# Project.net
KiCad netlist of a schematic drawn in EasyEDA Pro
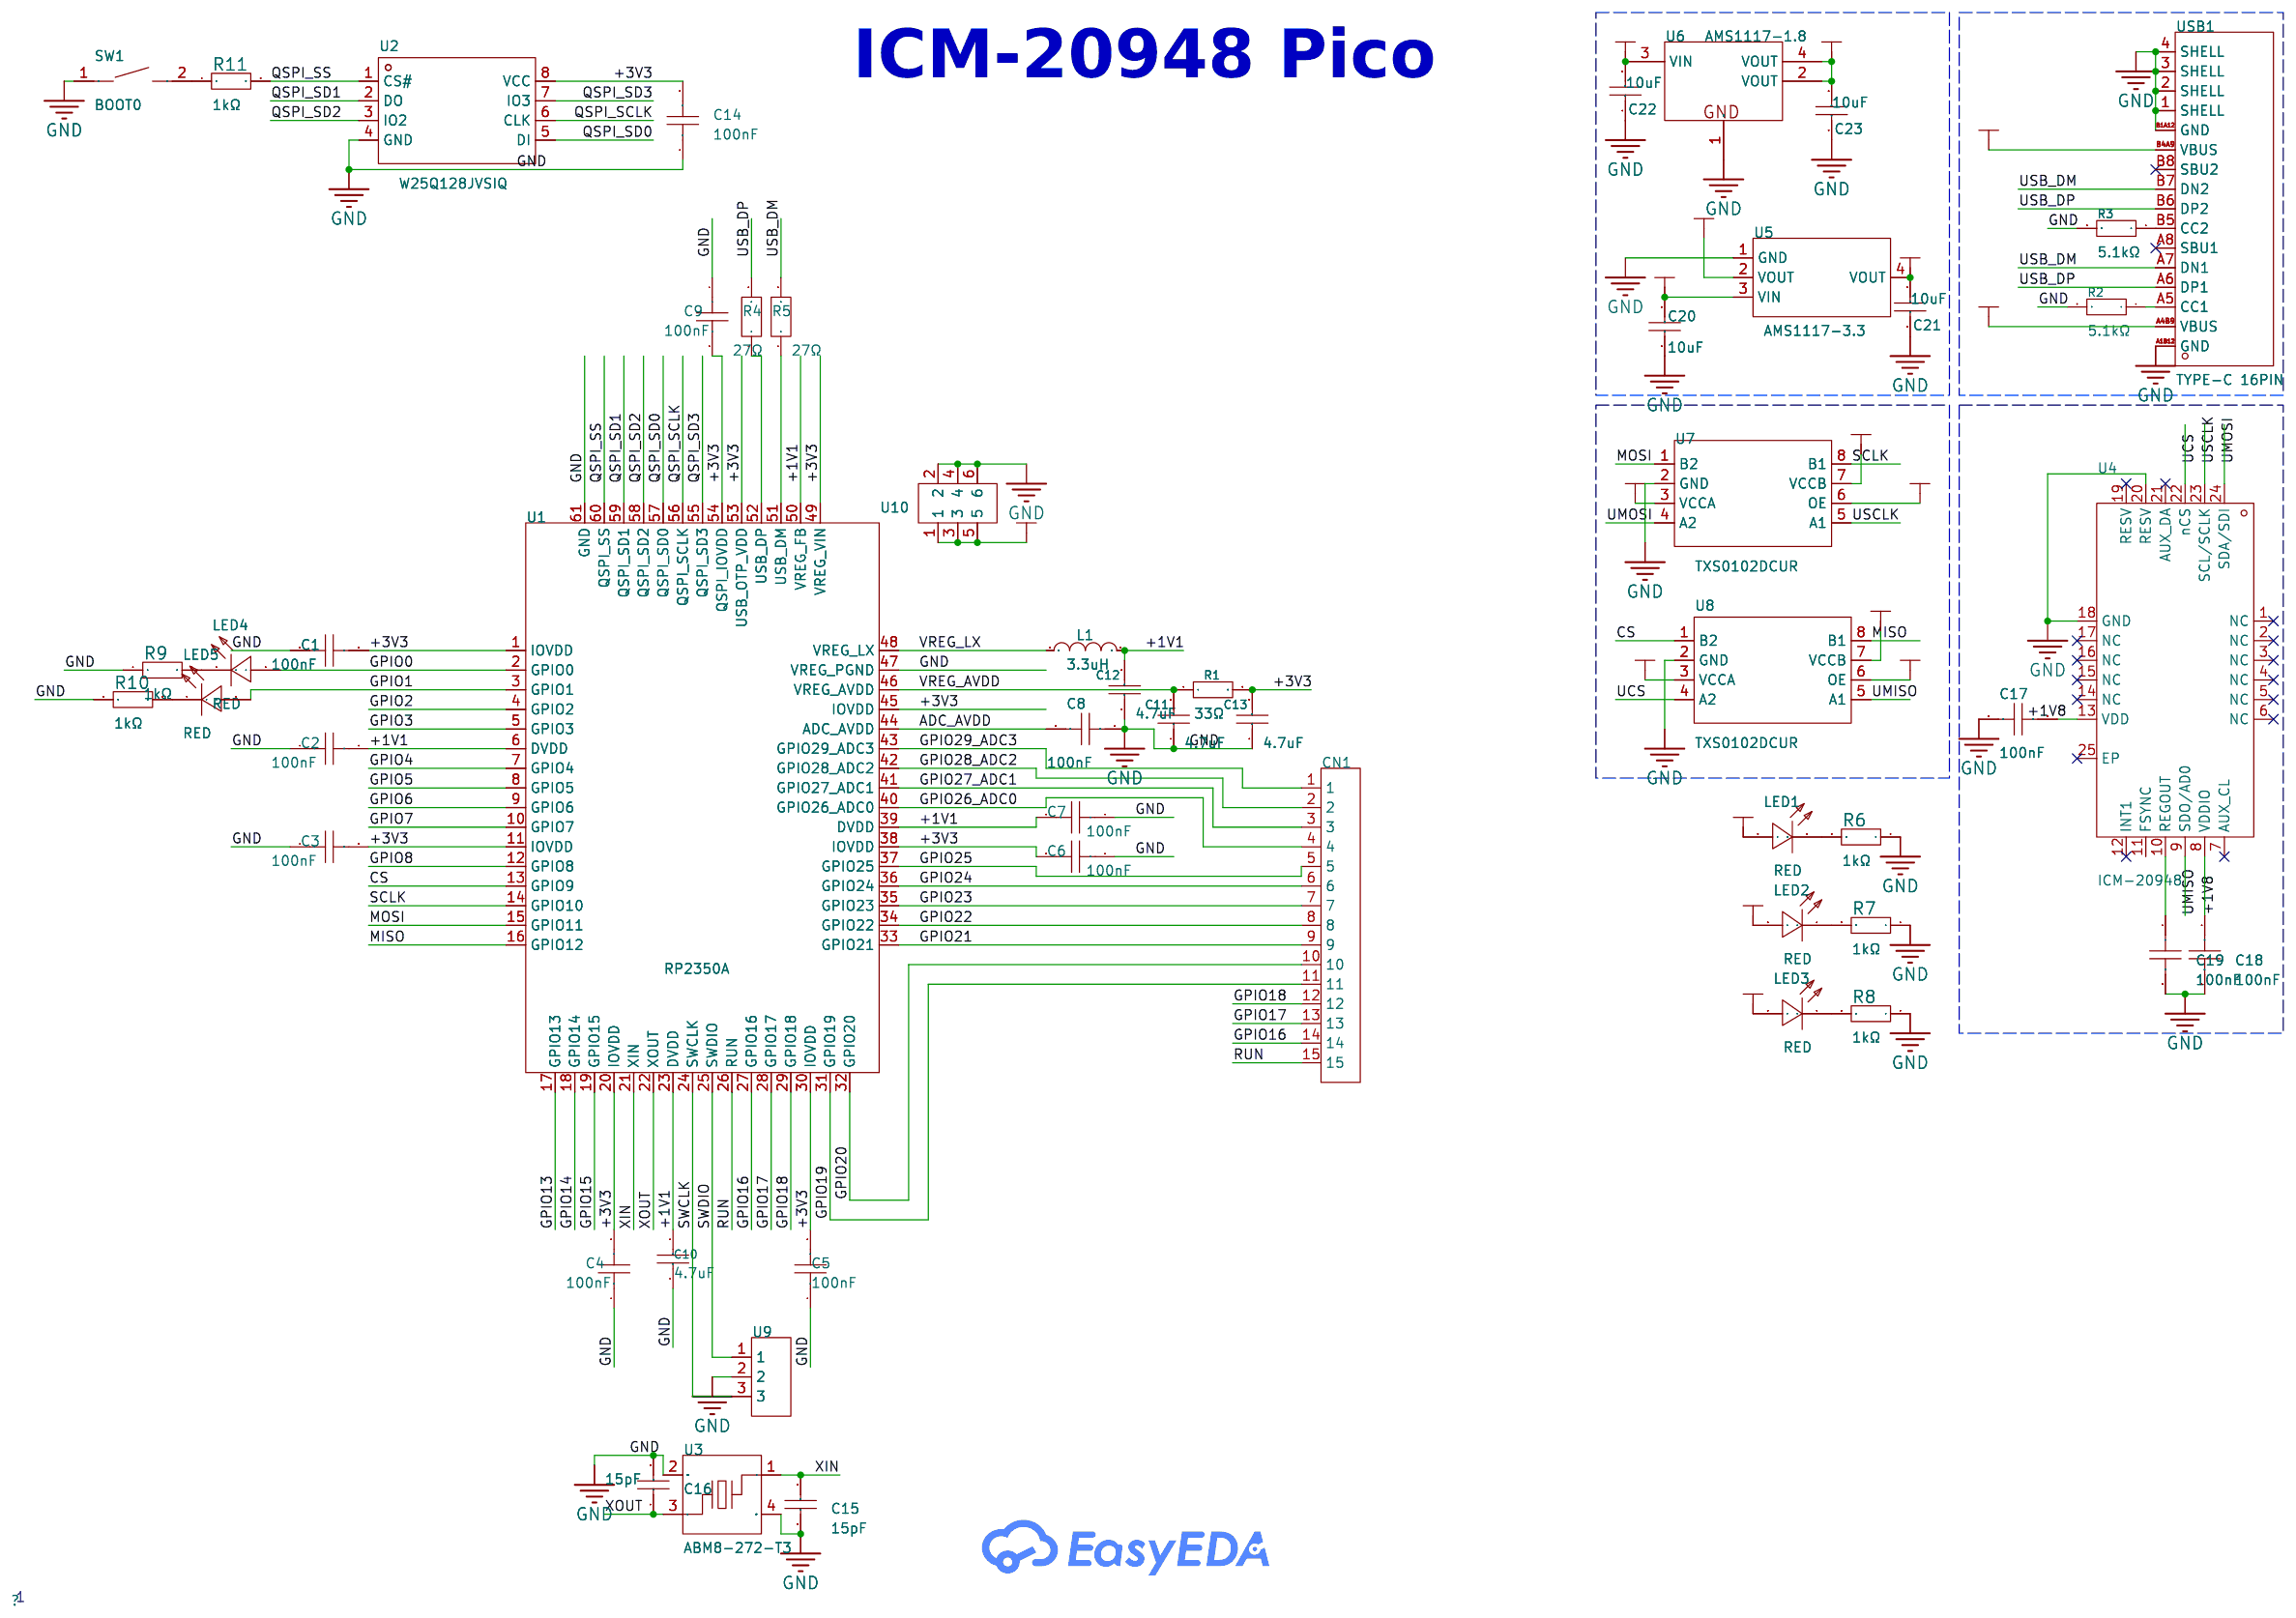
[diagram p0: schematic sheet]

(export (version "E")
  (design (tool "Eeschema 10.0.6"))
  (components
    (comp (ref "C1")
      (value "100nF")
      (footprint "easyedapro:C0402")
      (fields
        (field (name "Manufacturer Part") "CL05B104KO5NNNC")
        (field (name "Manufacturer") "SAMSUNG(三星)")
      )
      (libsource (lib "easyedapro") (part "CL05B104KO5NNNC"))
    )
    (comp (ref "C2")
      (value "100nF")
      (footprint "easyedapro:C0402")
      (fields
        (field (name "Manufacturer Part") "CL05B104KO5NNNC")
        (field (name "Manufacturer") "SAMSUNG(三星)")
      )
      (libsource (lib "easyedapro") (part "CL05B104KO5NNNC"))
    )
    (comp (ref "C3")
      (value "100nF")
      (footprint "easyedapro:C0402")
      (fields
        (field (name "Manufacturer Part") "CL05B104KO5NNNC")
        (field (name "Manufacturer") "SAMSUNG(三星)")
      )
      (libsource (lib "easyedapro") (part "CL05B104KO5NNNC"))
    )
    (comp (ref "C4")
      (value "100nF")
      (footprint "easyedapro:C0402")
      (fields
        (field (name "Manufacturer Part") "CL05B104KO5NNNC")
        (field (name "Manufacturer") "SAMSUNG(三星)")
      )
      (libsource (lib "easyedapro") (part "CL05B104KO5NNNC"))
    )
    (comp (ref "C5")
      (value "100nF")
      (footprint "easyedapro:C0402")
      (fields
        (field (name "Manufacturer Part") "CL05B104KO5NNNC")
        (field (name "Manufacturer") "SAMSUNG(三星)")
      )
      (libsource (lib "easyedapro") (part "CL05B104KO5NNNC"))
    )
    (comp (ref "C6")
      (value "100nF")
      (footprint "easyedapro:C0402")
      (fields
        (field (name "Manufacturer Part") "CL05B104KO5NNNC")
        (field (name "Manufacturer") "SAMSUNG(三星)")
      )
      (libsource (lib "easyedapro") (part "CL05B104KO5NNNC"))
    )
    (comp (ref "C7")
      (value "100nF")
      (footprint "easyedapro:C0402")
      (fields
        (field (name "Manufacturer Part") "CL05B104KO5NNNC")
        (field (name "Manufacturer") "SAMSUNG(三星)")
      )
      (libsource (lib "easyedapro") (part "CL05B104KO5NNNC"))
    )
    (comp (ref "C8")
      (value "100nF")
      (footprint "easyedapro:C0402")
      (fields
        (field (name "Manufacturer Part") "CL05B104KO5NNNC")
        (field (name "Manufacturer") "SAMSUNG(三星)")
      )
      (libsource (lib "easyedapro") (part "CL05B104KO5NNNC"))
    )
    (comp (ref "C9")
      (value "100nF")
      (footprint "easyedapro:C0402")
      (fields
        (field (name "Manufacturer Part") "CL05B104KO5NNNC")
        (field (name "Manufacturer") "SAMSUNG(三星)")
      )
      (libsource (lib "easyedapro") (part "CL05B104KO5NNNC"))
    )
    (comp (ref "C10")
      (value "4.7uF")
      (footprint "easyedapro:C0402")
      (fields
        (field (name "Manufacturer Part") "CL05A475MP5NRNC")
        (field (name "Manufacturer") "SAMSUNG(三星)")
      )
      (libsource (lib "easyedapro") (part "CL05A475MP5NRNC"))
    )
    (comp (ref "C11")
      (value "4.7uF")
      (footprint "easyedapro:C0402")
      (fields
        (field (name "Manufacturer Part") "CL05A475MP5NRNC")
        (field (name "Manufacturer") "SAMSUNG(三星)")
      )
      (libsource (lib "easyedapro") (part "CL05A475MP5NRNC"))
    )
    (comp (ref "C12")
      (value "4.7uF")
      (footprint "easyedapro:C0402")
      (fields
        (field (name "Manufacturer Part") "CL05A475MP5NRNC")
        (field (name "Manufacturer") "SAMSUNG(三星)")
      )
      (libsource (lib "easyedapro") (part "CL05A475MP5NRNC"))
    )
    (comp (ref "C13")
      (value "4.7uF")
      (footprint "easyedapro:C0402")
      (fields
        (field (name "Manufacturer Part") "CL05A475MP5NRNC")
        (field (name "Manufacturer") "SAMSUNG(三星)")
      )
      (libsource (lib "easyedapro") (part "CL05A475MP5NRNC"))
    )
    (comp (ref "C14")
      (value "100nF")
      (footprint "easyedapro:C0402")
      (fields
        (field (name "Manufacturer Part") "CL05B104KO5NNNC")
        (field (name "Manufacturer") "SAMSUNG(三星)")
      )
      (libsource (lib "easyedapro") (part "CL05B104KO5NNNC"))
    )
    (comp (ref "C15")
      (value "15pF")
      (footprint "easyedapro:C0402")
      (fields (field (name "Manufacturer Part") "0402CG150J500NT") (field (name "Manufacturer") "FH(风华)"))
      (libsource (lib "easyedapro") (part "0402CG150J500NT"))
    )
    (comp (ref "C16")
      (value "15pF")
      (footprint "easyedapro:C0402")
      (fields (field (name "Manufacturer Part") "0402CG150J500NT") (field (name "Manufacturer") "FH(风华)"))
      (libsource (lib "easyedapro") (part "0402CG150J500NT"))
    )
    (comp (ref "C17")
      (value "100nF")
      (footprint "easyedapro:C0402")
      (fields
        (field (name "Manufacturer Part") "CL05B104KO5NNNC")
        (field (name "Manufacturer") "SAMSUNG(三星)")
      )
      (libsource (lib "easyedapro") (part "CL05B104KO5NNNC"))
    )
    (comp (ref "C18")
      (value "100nF")
      (footprint "easyedapro:C0402")
      (fields
        (field (name "Manufacturer Part") "CL05B104KO5NNNC")
        (field (name "Manufacturer") "SAMSUNG(三星)")
      )
      (libsource (lib "easyedapro") (part "CL05B104KO5NNNC"))
    )
    (comp (ref "C19")
      (value "100nF")
      (footprint "easyedapro:C0402")
      (fields
        (field (name "Manufacturer Part") "CL05B104KO5NNNC")
        (field (name "Manufacturer") "SAMSUNG(三星)")
      )
      (libsource (lib "easyedapro") (part "CL05B104KO5NNNC"))
    )
    (comp (ref "C20")
      (value "10uF")
      (footprint "easyedapro:C0402")
      (fields
        (field (name "Manufacturer Part") "CL05A106MQ5NUNC")
        (field (name "Manufacturer") "SAMSUNG(三星)")
      )
      (libsource (lib "easyedapro") (part "CL05A106MQ5NUNC"))
    )
    (comp (ref "C21")
      (value "10uF")
      (footprint "easyedapro:C0402")
      (fields
        (field (name "Manufacturer Part") "CL05A106MQ5NUNC")
        (field (name "Manufacturer") "SAMSUNG(三星)")
      )
      (libsource (lib "easyedapro") (part "CL05A106MQ5NUNC"))
    )
    (comp (ref "C22")
      (value "10uF")
      (footprint "easyedapro:C0402")
      (fields
        (field (name "Manufacturer Part") "CL05A106MQ5NUNC")
        (field (name "Manufacturer") "SAMSUNG(三星)")
      )
      (libsource (lib "easyedapro") (part "CL05A106MQ5NUNC"))
    )
    (comp (ref "C23")
      (value "10uF")
      (footprint "easyedapro:C0402")
      (fields
        (field (name "Manufacturer Part") "CL05A106MQ5NUNC")
        (field (name "Manufacturer") "SAMSUNG(三星)")
      )
      (libsource (lib "easyedapro") (part "CL05A106MQ5NUNC"))
    )
    (comp (ref "CN1")
      (value "排母插针1X15P")
      (footprint "easyedapro:CONN-TH_15P-L38.5-W2.4-P2.54")
      (libsource (lib "easyedapro") (part "排母插针1X15P"))
    )
    (comp (ref "L1")
      (value "3.3uH")
      (footprint "easyedapro:IND-SMD_L2.0-W1.6_AOTA-B201610S3R3-101-T")
      (fields (field (name "Manufacturer") "ABRACON"))
      (libsource (lib "easyedapro") (part "AOTA-B201610S3R3-101-T"))
    )
    (comp (ref "LED1")
      (value "RED")
      (footprint "easyedapro:LED0603-RD")
      (fields (field (name "Manufacturer") "KENTO"))
      (libsource (lib "easyedapro") (part "KT-0603R"))
    )
    (comp (ref "LED2")
      (value "RED")
      (footprint "easyedapro:LED0603-RD")
      (fields (field (name "Manufacturer") "KENTO"))
      (libsource (lib "easyedapro") (part "KT-0603R"))
    )
    (comp (ref "LED3")
      (value "RED")
      (footprint "easyedapro:LED0603-RD")
      (fields (field (name "Manufacturer") "KENTO"))
      (libsource (lib "easyedapro") (part "KT-0603R"))
    )
    (comp (ref "LED4")
      (value "RED")
      (footprint "easyedapro:LED0603-RD")
      (fields (field (name "Manufacturer") "KENTO"))
      (libsource (lib "easyedapro") (part "KT-0603R"))
    )
    (comp (ref "LED5")
      (value "RED")
      (footprint "easyedapro:LED0603-RD")
      (fields (field (name "Manufacturer") "KENTO"))
      (libsource (lib "easyedapro") (part "KT-0603R"))
    )
    (comp (ref "R1")
      (value "33Ω")
      (footprint "easyedapro:R0402")
      (fields
        (field (name "Manufacturer Part") "0402WGF330JTCE")
        (field (name "Manufacturer") "UNI-ROYAL(厚声)")
      )
      (libsource (lib "easyedapro") (part "0402WGF330JTCE"))
    )
    (comp (ref "R2")
      (value "5.1kΩ")
      (footprint "easyedapro:R0402")
      (fields
        (field (name "Manufacturer Part") "0402WGF5101TCE")
        (field (name "Manufacturer") "UNI-ROYAL(厚声)")
      )
      (libsource (lib "easyedapro") (part "0402WGF5101TCE"))
    )
    (comp (ref "R3")
      (value "5.1kΩ")
      (footprint "easyedapro:R0402")
      (fields
        (field (name "Manufacturer Part") "0402WGF5101TCE")
        (field (name "Manufacturer") "UNI-ROYAL(厚声)")
      )
      (libsource (lib "easyedapro") (part "0402WGF5101TCE"))
    )
    (comp (ref "R4")
      (value "27Ω")
      (footprint "easyedapro:R0402")
      (fields (field (name "Manufacturer Part") "WR04X270JTL") (field (name "Manufacturer") "Walsin(华新科)"))
      (libsource (lib "easyedapro") (part "WR04X270 JTL"))
    )
    (comp (ref "R5")
      (value "27Ω")
      (footprint "easyedapro:R0402")
      (fields (field (name "Manufacturer Part") "WR04X270JTL") (field (name "Manufacturer") "Walsin(华新科)"))
      (libsource (lib "easyedapro") (part "WR04X270 JTL"))
    )
    (comp (ref "R6")
      (value "1kΩ")
      (footprint "easyedapro:R0402")
      (fields
        (field (name "Manufacturer Part") "0402WGF1001TCE")
        (field (name "Manufacturer") "UNI-ROYAL(厚声)")
      )
      (libsource (lib "easyedapro") (part "0402WGF1001TCE"))
    )
    (comp (ref "R7")
      (value "1kΩ")
      (footprint "easyedapro:R0402")
      (fields
        (field (name "Manufacturer Part") "0402WGF1001TCE")
        (field (name "Manufacturer") "UNI-ROYAL(厚声)")
      )
      (libsource (lib "easyedapro") (part "0402WGF1001TCE"))
    )
    (comp (ref "R8")
      (value "1kΩ")
      (footprint "easyedapro:R0402")
      (fields
        (field (name "Manufacturer Part") "0402WGF1001TCE")
        (field (name "Manufacturer") "UNI-ROYAL(厚声)")
      )
      (libsource (lib "easyedapro") (part "0402WGF1001TCE"))
    )
    (comp (ref "R9")
      (value "1kΩ")
      (footprint "easyedapro:R0402")
      (fields
        (field (name "Manufacturer Part") "0402WGF1001TCE")
        (field (name "Manufacturer") "UNI-ROYAL(厚声)")
      )
      (libsource (lib "easyedapro") (part "0402WGF1001TCE"))
    )
    (comp (ref "R10")
      (value "1kΩ")
      (footprint "easyedapro:R0402")
      (fields
        (field (name "Manufacturer Part") "0402WGF1001TCE")
        (field (name "Manufacturer") "UNI-ROYAL(厚声)")
      )
      (libsource (lib "easyedapro") (part "0402WGF1001TCE"))
    )
    (comp (ref "R11")
      (value "1kΩ")
      (footprint "easyedapro:R0402")
      (fields
        (field (name "Manufacturer Part") "0402WGF1001TCE")
        (field (name "Manufacturer") "UNI-ROYAL(厚声)")
      )
      (libsource (lib "easyedapro") (part "0402WGF1001TCE"))
    )
    (comp (ref "SW1")
      (value "BOOT0")
      (footprint "easyedapro:SW-SMD_L3.9-W3.0-P4.45")
      (fields (field (name "Manufacturer") "XUNPU(讯普)"))
      (libsource (lib "easyedapro") (part "TS-1088-AR02016"))
    )
    (comp (ref "U1")
      (value "RP2350A")
      (footprint "easyedapro:QFN-60_L7.0-W7.0-P0.40-TL-EP3.4")
      (fields (field (name "Manufacturer") "Raspberry Pi(树莓派)"))
      (libsource (lib "easyedapro") (part "RP2350A_C42411118"))
    )
    (comp (ref "U2")
      (value "W25Q128JVSIQ")
      (footprint "easyedapro:SOIC-8_L5.3-W5.3-P1.27-LS8.0-BL")
      (fields (field (name "Manufacturer") "WINBOND(华邦)"))
      (libsource (lib "easyedapro") (part "W25Q128JVSIQTR"))
    )
    (comp (ref "U3")
      (value "ABM8-272-T3")
      (footprint "easyedapro:CRYSTAL-SMD_4P-L3.2-W2.5-BL")
      (fields (field (name "Manufacturer") "ABRACON"))
      (libsource (lib "easyedapro") (part "ABM8-272-T3_C20625731"))
    )
    (comp (ref "U4")
      (value "ICM-20948")
      (footprint "easyedapro:QFN-24_L3.0-W3.0-P0.40-BL-EP")
      (fields (field (name "Manufacturer") "TDK InvenSense(应美盛)"))
      (libsource (lib "easyedapro") (part "ICM-20948"))
    )
    (comp (ref "U5")
      (value "AMS1117-3.3")
      (footprint "easyedapro:SOT-223-3_L6.5-W3.4-P2.30-LS7.0-BR")
      (fields (field (name "Manufacturer") "AMS"))
      (libsource (lib "easyedapro") (part "AMS1117-3.3"))
    )
    (comp (ref "U6")
      (value "AMS1117-1.8")
      (footprint "easyedapro:SOT-223-4_L6.5-W3.5-P2.30-LS7.0-BR")
      (fields (field (name "Manufacturer") "PUOLOP(迪浦)"))
      (libsource (lib "easyedapro") (part "AMS1117-1.8_C351432"))
    )
    (comp (ref "U7")
      (value "TXS0102DCUR")
      (footprint "easyedapro:VSON8_L2.0-W2.3-P0.50-LS3.1-BL")
      (fields (field (name "Manufacturer") "TI(德州仪器)"))
      (libsource (lib "easyedapro") (part "TXS0102DCUR"))
    )
    (comp (ref "U8")
      (value "TXS0102DCUR")
      (footprint "easyedapro:VSON8_L2.0-W2.3-P0.50-LS3.1-BL")
      (fields (field (name "Manufacturer") "TI(德州仪器)"))
      (libsource (lib "easyedapro") (part "TXS0102DCUR"))
    )
    (comp (ref "U9")
      (value "HB-PH3-25413PB2GOP")
      (footprint "easyedapro:HDR-TH_3P-P2.54-V-M")
      (fields (field (name "Manufacturer") "HANBO(汉博)"))
      (libsource (lib "easyedapro") (part "HB-PH3-25413PB2GOP"))
    )
    (comp (ref "U10")
      (value "ZX-PZ2.54-2-3PZZ")
      (footprint "easyedapro:HDR-TH_6P-P2.54-V-M-R2-C3-S2.54-1")
      (fields (field (name "Manufacturer") "Megastar(兆星)"))
      (libsource (lib "easyedapro") (part "ZX-PZ2.54-2-3PZZ"))
    )
    (comp (ref "USB1")
      (value "TYPE-C 16PIN")
      (footprint "easyedapro:USB-C-SMD_TYPE-C16PIN")
      (fields (field (name "Manufacturer") "SHOU HAN(首韩)"))
      (libsource (lib "easyedapro") (part "TYPE-C16PIN"))
    )
  )
  (nets
    (net (code "1") (name "+1V8") (class "Default")
      (node (ref "C17") (pin "2") (pinfunction "2_2") (pintype "unspecified"))
      (node (ref "C18") (pin "1") (pinfunction "1_1") (pintype "unspecified"))
      (node (ref "C23") (pin "2") (pinfunction "2_2") (pintype "input"))
      (node (ref "LED3") (pin "2") (pinfunction "A_2") (pintype "unspecified"))
      (node (ref "U4") (pin "13") (pinfunction "VDD_13") (pintype "unspecified"))
      (node (ref "U4") (pin "8") (pinfunction "VDDIO_8") (pintype "unspecified"))
      (node (ref "U6") (pin "2") (pinfunction "VOUT_2") (pintype "unspecified"))
      (node (ref "U6") (pin "4") (pinfunction "VOUT_4") (pintype "unspecified"))
      (node (ref "U7") (pin "3") (pinfunction "VCCA_3") (pintype "unspecified"))
      (node (ref "U7") (pin "6") (pinfunction "OE_6") (pintype "unspecified"))
      (node (ref "U8") (pin "3") (pinfunction "VCCA_3") (pintype "unspecified"))
      (node (ref "U8") (pin "6") (pinfunction "OE_6") (pintype "unspecified"))
    )
    (net (code "2") (name "+3V3") (class "Default")
      (node (ref "C1") (pin "2") (pinfunction "2_2") (pintype "unspecified"))
      (node (ref "C13") (pin "2") (pinfunction "2_2") (pintype "input"))
      (node (ref "C14") (pin "2") (pinfunction "2_2") (pintype "unspecified"))
      (node (ref "C21") (pin "2") (pinfunction "2_2") (pintype "input"))
      (node (ref "C3") (pin "2") (pinfunction "2_2") (pintype "unspecified"))
      (node (ref "C4") (pin "2") (pinfunction "2_2") (pintype "unspecified"))
      (node (ref "C5") (pin "2") (pinfunction "2_2") (pintype "unspecified"))
      (node (ref "C6") (pin "2") (pinfunction "2_2") (pintype "unspecified"))
      (node (ref "C9") (pin "2") (pinfunction "2_2") (pintype "unspecified"))
      (node (ref "LED2") (pin "2") (pinfunction "A_2") (pintype "unspecified"))
      (node (ref "R1") (pin "2") (pinfunction "2_2") (pintype "input"))
      (node (ref "U1") (pin "1") (pinfunction "IOVDD_1") (pintype "unspecified"))
      (node (ref "U1") (pin "11") (pinfunction "IOVDD_11") (pintype "unspecified"))
      (node (ref "U1") (pin "20") (pinfunction "IOVDD_20") (pintype "unspecified"))
      (node (ref "U1") (pin "30") (pinfunction "IOVDD_30") (pintype "unspecified"))
      (node (ref "U1") (pin "38") (pinfunction "IOVDD_38") (pintype "unspecified"))
      (node (ref "U1") (pin "45") (pinfunction "IOVDD_45") (pintype "unspecified"))
      (node (ref "U1") (pin "49") (pinfunction "VREG_VIN_49") (pintype "unspecified"))
      (node (ref "U1") (pin "53") (pinfunction "USB_OTP_VDD_53") (pintype "unspecified"))
      (node (ref "U1") (pin "54") (pinfunction "QSPI_IOVDD_54") (pintype "unspecified"))
      (node (ref "U10") (pin "1") (pinfunction "1_1") (pintype "unspecified"))
      (node (ref "U10") (pin "3") (pinfunction "3_3") (pintype "unspecified"))
      (node (ref "U10") (pin "5") (pinfunction "5_5") (pintype "unspecified"))
      (node (ref "U2") (pin "8") (pinfunction "VCC_8") (pintype "unspecified"))
      (node (ref "U5") (pin "2") (pinfunction "VOUT_2") (pintype "unspecified"))
      (node (ref "U5") (pin "4") (pinfunction "VOUT_4") (pintype "unspecified"))
      (node (ref "U7") (pin "7") (pinfunction "VCCB_7") (pintype "unspecified"))
      (node (ref "U8") (pin "7") (pinfunction "VCCB_7") (pintype "unspecified"))
    )
    (net (code "3") (name "/+1V1") (class "Default")
      (node (ref "C10") (pin "2") (pinfunction "2_2") (pintype "input"))
      (node (ref "C12") (pin "2") (pinfunction "2_2") (pintype "input"))
      (node (ref "C2") (pin "2") (pinfunction "2_2") (pintype "unspecified"))
      (node (ref "C7") (pin "2") (pinfunction "2_2") (pintype "unspecified"))
      (node (ref "L1") (pin "2") (pinfunction "2_2") (pintype "unspecified"))
      (node (ref "U1") (pin "23") (pinfunction "DVDD_23") (pintype "unspecified"))
      (node (ref "U1") (pin "39") (pinfunction "DVDD_39") (pintype "unspecified"))
      (node (ref "U1") (pin "50") (pinfunction "VREG_FB_50") (pintype "unspecified"))
      (node (ref "U1") (pin "6") (pinfunction "DVDD_6") (pintype "unspecified"))
    )
    (net (code "4") (name "/ADC_AVDD") (class "Default")
      (node (ref "C8") (pin "2") (pinfunction "2_2") (pintype "unspecified"))
      (node (ref "U1") (pin "44") (pinfunction "ADC_AVDD_44") (pintype "unspecified"))
    )
    (net (code "5") (name "/CS") (class "Default")
      (node (ref "U1") (pin "13") (pinfunction "GPIO9_13") (pintype "unspecified"))
      (node (ref "U8") (pin "1") (pinfunction "B2_1") (pintype "unspecified"))
    )
    (net (code "6") (name "/GPIO0") (class "Default")
      (node (ref "LED4") (pin "2") (pinfunction "A_2") (pintype "unspecified"))
      (node (ref "U1") (pin "2") (pinfunction "GPIO0_2") (pintype "unspecified"))
    )
    (net (code "7") (name "/GPIO1") (class "Default")
      (node (ref "LED5") (pin "2") (pinfunction "A_2") (pintype "unspecified"))
      (node (ref "U1") (pin "3") (pinfunction "GPIO1_3") (pintype "unspecified"))
    )
    (net (code "8") (name "/GPIO2") (class "Default")
      (node (ref "U1") (pin "4") (pinfunction "GPIO2_4") (pintype "unspecified"))
    )
    (net (code "9") (name "/GPIO3") (class "Default")
      (node (ref "U1") (pin "5") (pinfunction "GPIO3_5") (pintype "unspecified"))
    )
    (net (code "10") (name "/GPIO4") (class "Default")
      (node (ref "U1") (pin "7") (pinfunction "GPIO4_7") (pintype "unspecified"))
    )
    (net (code "11") (name "/GPIO5") (class "Default")
      (node (ref "U1") (pin "8") (pinfunction "GPIO5_8") (pintype "unspecified"))
    )
    (net (code "12") (name "/GPIO6") (class "Default")
      (node (ref "U1") (pin "9") (pinfunction "GPIO6_9") (pintype "unspecified"))
    )
    (net (code "13") (name "/GPIO7") (class "Default")
      (node (ref "U1") (pin "10") (pinfunction "GPIO7_10") (pintype "unspecified"))
    )
    (net (code "14") (name "/GPIO8") (class "Default")
      (node (ref "U1") (pin "12") (pinfunction "GPIO8_12") (pintype "unspecified"))
    )
    (net (code "15") (name "/GPIO13") (class "Default")
      (node (ref "U1") (pin "17") (pinfunction "GPIO13_17") (pintype "unspecified"))
    )
    (net (code "16") (name "/GPIO14") (class "Default")
      (node (ref "U1") (pin "18") (pinfunction "GPIO14_18") (pintype "unspecified"))
    )
    (net (code "17") (name "/GPIO15") (class "Default")
      (node (ref "U1") (pin "19") (pinfunction "GPIO15_19") (pintype "unspecified"))
    )
    (net (code "18") (name "/GPIO16") (class "Default")
      (node (ref "CN1") (pin "14") (pinfunction "14_14") (pintype "unspecified"))
      (node (ref "U1") (pin "27") (pinfunction "GPIO16_27") (pintype "unspecified"))
    )
    (net (code "19") (name "/GPIO17") (class "Default")
      (node (ref "CN1") (pin "13") (pinfunction "13_13") (pintype "unspecified"))
      (node (ref "U1") (pin "28") (pinfunction "GPIO17_28") (pintype "unspecified"))
    )
    (net (code "20") (name "/GPIO18") (class "Default")
      (node (ref "CN1") (pin "12") (pinfunction "12_12") (pintype "unspecified"))
      (node (ref "U1") (pin "29") (pinfunction "GPIO18_29") (pintype "unspecified"))
    )
    (net (code "21") (name "/GPIO19") (class "Default")
      (node (ref "CN1") (pin "11") (pinfunction "11_11") (pintype "unspecified"))
      (node (ref "U1") (pin "31") (pinfunction "GPIO19_31") (pintype "unspecified"))
    )
    (net (code "22") (name "/GPIO20") (class "Default")
      (node (ref "CN1") (pin "10") (pinfunction "10_10") (pintype "unspecified"))
      (node (ref "U1") (pin "32") (pinfunction "GPIO20_32") (pintype "unspecified"))
    )
    (net (code "23") (name "/GPIO21") (class "Default")
      (node (ref "CN1") (pin "9") (pinfunction "9_9") (pintype "unspecified"))
      (node (ref "U1") (pin "33") (pinfunction "GPIO21_33") (pintype "unspecified"))
    )
    (net (code "24") (name "/GPIO22") (class "Default")
      (node (ref "CN1") (pin "8") (pinfunction "8_8") (pintype "unspecified"))
      (node (ref "U1") (pin "34") (pinfunction "GPIO22_34") (pintype "unspecified"))
    )
    (net (code "25") (name "/GPIO23") (class "Default")
      (node (ref "CN1") (pin "7") (pinfunction "7_7") (pintype "unspecified"))
      (node (ref "U1") (pin "35") (pinfunction "GPIO23_35") (pintype "unspecified"))
    )
    (net (code "26") (name "/GPIO24") (class "Default")
      (node (ref "CN1") (pin "6") (pinfunction "6_6") (pintype "unspecified"))
      (node (ref "U1") (pin "36") (pinfunction "GPIO24_36") (pintype "unspecified"))
    )
    (net (code "27") (name "/GPIO25") (class "Default")
      (node (ref "CN1") (pin "5") (pinfunction "5_5") (pintype "unspecified"))
      (node (ref "U1") (pin "37") (pinfunction "GPIO25_37") (pintype "unspecified"))
    )
    (net (code "28") (name "/GPIO26_ADC0") (class "Default")
      (node (ref "CN1") (pin "4") (pinfunction "4_4") (pintype "unspecified"))
      (node (ref "U1") (pin "40") (pinfunction "GPIO26_ADC0_40") (pintype "unspecified"))
    )
    (net (code "29") (name "/GPIO27_ADC1") (class "Default")
      (node (ref "CN1") (pin "3") (pinfunction "3_3") (pintype "unspecified"))
      (node (ref "U1") (pin "41") (pinfunction "GPIO27_ADC1_41") (pintype "unspecified"))
    )
    (net (code "30") (name "/GPIO28_ADC2") (class "Default")
      (node (ref "CN1") (pin "2") (pinfunction "2_2") (pintype "unspecified"))
      (node (ref "U1") (pin "42") (pinfunction "GPIO28_ADC2_42") (pintype "unspecified"))
    )
    (net (code "31") (name "/GPIO29_ADC3") (class "Default")
      (node (ref "CN1") (pin "1") (pinfunction "1_1") (pintype "unspecified"))
      (node (ref "U1") (pin "43") (pinfunction "GPIO29_ADC3_43") (pintype "unspecified"))
    )
    (net (code "32") (name "/MISO") (class "Default")
      (node (ref "U1") (pin "16") (pinfunction "GPIO12_16") (pintype "unspecified"))
      (node (ref "U8") (pin "8") (pinfunction "B1_8") (pintype "unspecified"))
    )
    (net (code "33") (name "/MOSI") (class "Default")
      (node (ref "U1") (pin "15") (pinfunction "GPIO11_15") (pintype "unspecified"))
      (node (ref "U7") (pin "1") (pinfunction "B2_1") (pintype "unspecified"))
    )
    (net (code "34") (name "/QSPI_SCLK") (class "Default")
      (node (ref "U1") (pin "56") (pinfunction "QSPI_SCLK_56") (pintype "unspecified"))
      (node (ref "U2") (pin "6") (pinfunction "CLK_6") (pintype "unspecified"))
    )
    (net (code "35") (name "/QSPI_SD0") (class "Default")
      (node (ref "U1") (pin "57") (pinfunction "QSPI_SD0_57") (pintype "unspecified"))
      (node (ref "U2") (pin "5") (pinfunction "DI_5") (pintype "unspecified"))
    )
    (net (code "36") (name "/QSPI_SD1") (class "Default")
      (node (ref "U1") (pin "59") (pinfunction "QSPI_SD1_59") (pintype "unspecified"))
      (node (ref "U2") (pin "2") (pinfunction "DO_2") (pintype "unspecified"))
    )
    (net (code "37") (name "/QSPI_SD2") (class "Default")
      (node (ref "U1") (pin "58") (pinfunction "QSPI_SD2_58") (pintype "unspecified"))
      (node (ref "U2") (pin "3") (pinfunction "IO2_3") (pintype "unspecified"))
    )
    (net (code "38") (name "/QSPI_SD3") (class "Default")
      (node (ref "U1") (pin "55") (pinfunction "QSPI_SD3_55") (pintype "unspecified"))
      (node (ref "U2") (pin "7") (pinfunction "IO3_7") (pintype "unspecified"))
    )
    (net (code "39") (name "/QSPI_SS") (class "Default")
      (node (ref "R11") (pin "2") (pinfunction "2_2") (pintype "input"))
      (node (ref "U1") (pin "60") (pinfunction "QSPI_SS_60") (pintype "unspecified"))
      (node (ref "U2") (pin "1") (pinfunction "CS#_1") (pintype "unspecified"))
    )
    (net (code "40") (name "/RUN") (class "Default")
      (node (ref "CN1") (pin "15") (pinfunction "15_15") (pintype "unspecified"))
      (node (ref "U1") (pin "26") (pinfunction "RUN_26") (pintype "unspecified"))
    )
    (net (code "41") (name "/SCLK") (class "Default")
      (node (ref "U1") (pin "14") (pinfunction "GPIO10_14") (pintype "unspecified"))
      (node (ref "U7") (pin "8") (pinfunction "B1_8") (pintype "unspecified"))
    )
    (net (code "42") (name "/SWCLK") (class "Default")
      (node (ref "U1") (pin "24") (pinfunction "SWCLK_24") (pintype "unspecified"))
      (node (ref "U9") (pin "3") (pinfunction "3_3") (pintype "unspecified"))
    )
    (net (code "43") (name "/SWDIO") (class "Default")
      (node (ref "U1") (pin "25") (pinfunction "SWDIO_25") (pintype "unspecified"))
      (node (ref "U9") (pin "1") (pinfunction "1_1") (pintype "unspecified"))
    )
    (net (code "44") (name "/UCS") (class "Default")
      (node (ref "U4") (pin "22") (pinfunction "nCS_22") (pintype "unspecified"))
      (node (ref "U8") (pin "4") (pinfunction "A2_4") (pintype "unspecified"))
    )
    (net (code "45") (name "/UMISO") (class "Default")
      (node (ref "U4") (pin "9") (pinfunction "SDO/AD0_9") (pintype "unspecified"))
      (node (ref "U8") (pin "5") (pinfunction "A1_5") (pintype "unspecified"))
    )
    (net (code "46") (name "/UMOSI") (class "Default")
      (node (ref "U4") (pin "24") (pinfunction "SDA/SDI_24") (pintype "unspecified"))
      (node (ref "U7") (pin "4") (pinfunction "A2_4") (pintype "unspecified"))
    )
    (net (code "47") (name "/USB_DM") (class "Default")
      (node (ref "R5") (pin "2") (pinfunction "2_2") (pintype "unspecified"))
      (node (ref "USB1") (pin "A7") (pinfunction "DN1_A7") (pintype "unspecified"))
      (node (ref "USB1") (pin "B7") (pinfunction "DN2_B7") (pintype "unspecified"))
    )
    (net (code "48") (name "/USB_DP") (class "Default")
      (node (ref "R4") (pin "2") (pinfunction "2_2") (pintype "unspecified"))
      (node (ref "USB1") (pin "A6") (pinfunction "DP1_A6") (pintype "unspecified"))
      (node (ref "USB1") (pin "B6") (pinfunction "DP2_B6") (pintype "unspecified"))
    )
    (net (code "49") (name "/USCLK") (class "Default")
      (node (ref "U4") (pin "23") (pinfunction "SCL/SCLK_23") (pintype "unspecified"))
      (node (ref "U7") (pin "5") (pinfunction "A1_5") (pintype "unspecified"))
    )
    (net (code "50") (name "/VREG_AVDD") (class "Default")
      (node (ref "C11") (pin "2") (pinfunction "2_2") (pintype "input"))
      (node (ref "R1") (pin "1") (pinfunction "1_1") (pintype "input"))
      (node (ref "U1") (pin "46") (pinfunction "VREG_AVDD_46") (pintype "unspecified"))
    )
    (net (code "51") (name "/VREG_LX") (class "Default")
      (node (ref "L1") (pin "1") (pinfunction "1_1") (pintype "unspecified"))
      (node (ref "U1") (pin "48") (pinfunction "VREG_LX_48") (pintype "unspecified"))
    )
    (net (code "52") (name "/XIN") (class "Default")
      (node (ref "C15") (pin "2") (pinfunction "2_2") (pintype "input"))
      (node (ref "U1") (pin "21") (pinfunction "XIN_21") (pintype "unspecified"))
      (node (ref "U3") (pin "1") (pinfunction "1_1") (pintype "input"))
    )
    (net (code "53") (name "/XOUT") (class "Default")
      (node (ref "C16") (pin "1") (pinfunction "1_1") (pintype "input"))
      (node (ref "U1") (pin "22") (pinfunction "XOUT_22") (pintype "unspecified"))
      (node (ref "U3") (pin "3") (pinfunction "3_3") (pintype "input"))
    )
    (net (code "54") (name "GND") (class "Default")
      (node (ref "C1") (pin "1") (pinfunction "1_1") (pintype "unspecified"))
      (node (ref "C10") (pin "1") (pinfunction "1_1") (pintype "input"))
      (node (ref "C11") (pin "1") (pinfunction "1_1") (pintype "input"))
      (node (ref "C12") (pin "1") (pinfunction "1_1") (pintype "input"))
      (node (ref "C13") (pin "1") (pinfunction "1_1") (pintype "input"))
      (node (ref "C14") (pin "1") (pinfunction "1_1") (pintype "unspecified"))
      (node (ref "C15") (pin "1") (pinfunction "1_1") (pintype "input"))
      (node (ref "C16") (pin "2") (pinfunction "2_2") (pintype "input"))
      (node (ref "C17") (pin "1") (pinfunction "1_1") (pintype "unspecified"))
      (node (ref "C18") (pin "2") (pinfunction "2_2") (pintype "unspecified"))
      (node (ref "C19") (pin "2") (pinfunction "2_2") (pintype "unspecified"))
      (node (ref "C2") (pin "1") (pinfunction "1_1") (pintype "unspecified"))
      (node (ref "C20") (pin "1") (pinfunction "1_1") (pintype "input"))
      (node (ref "C21") (pin "1") (pinfunction "1_1") (pintype "input"))
      (node (ref "C22") (pin "1") (pinfunction "1_1") (pintype "input"))
      (node (ref "C23") (pin "1") (pinfunction "1_1") (pintype "input"))
      (node (ref "C3") (pin "1") (pinfunction "1_1") (pintype "unspecified"))
      (node (ref "C4") (pin "1") (pinfunction "1_1") (pintype "unspecified"))
      (node (ref "C5") (pin "1") (pinfunction "1_1") (pintype "unspecified"))
      (node (ref "C6") (pin "1") (pinfunction "1_1") (pintype "unspecified"))
      (node (ref "C7") (pin "1") (pinfunction "1_1") (pintype "unspecified"))
      (node (ref "C8") (pin "1") (pinfunction "1_1") (pintype "unspecified"))
      (node (ref "C9") (pin "1") (pinfunction "1_1") (pintype "unspecified"))
      (node (ref "R10") (pin "1") (pinfunction "1_1") (pintype "input"))
      (node (ref "R2") (pin "2") (pinfunction "2_2") (pintype "input"))
      (node (ref "R3") (pin "2") (pinfunction "2_2") (pintype "input"))
      (node (ref "R6") (pin "1") (pinfunction "1_1") (pintype "input"))
      (node (ref "R7") (pin "1") (pinfunction "1_1") (pintype "input"))
      (node (ref "R8") (pin "1") (pinfunction "1_1") (pintype "input"))
      (node (ref "R9") (pin "1") (pinfunction "1_1") (pintype "input"))
      (node (ref "SW1") (pin "1") (pinfunction "1_1") (pintype "unspecified"))
      (node (ref "U1") (pin "47") (pinfunction "VREG_PGND_47") (pintype "unspecified"))
      (node (ref "U1") (pin "61") (pinfunction "GND_61") (pintype "unspecified"))
      (node (ref "U10") (pin "2") (pinfunction "2_2") (pintype "unspecified"))
      (node (ref "U10") (pin "4") (pinfunction "4_4") (pintype "unspecified"))
      (node (ref "U10") (pin "6") (pinfunction "6_6") (pintype "unspecified"))
      (node (ref "U2") (pin "4") (pinfunction "GND_4") (pintype "unspecified"))
      (node (ref "U3") (pin "2") (pinfunction "GND_2") (pintype "input"))
      (node (ref "U3") (pin "4") (pinfunction "GND_4") (pintype "input"))
      (node (ref "U4") (pin "18") (pinfunction "GND_18") (pintype "unspecified"))
      (node (ref "U4") (pin "20") (pinfunction "RESV_20") (pintype "unspecified"))
      (node (ref "U5") (pin "1") (pinfunction "GND_1") (pintype "unspecified"))
      (node (ref "U6") (pin "1") (pinfunction "GND_1") (pintype "unspecified"))
      (node (ref "U7") (pin "2") (pinfunction "GND_2") (pintype "unspecified"))
      (node (ref "U8") (pin "2") (pinfunction "GND_2") (pintype "unspecified"))
      (node (ref "U9") (pin "2") (pinfunction "2_2") (pintype "unspecified"))
      (node (ref "USB1") (pin "1") (pinfunction "SHELL_1") (pintype "unspecified"))
      (node (ref "USB1") (pin "2") (pinfunction "SHELL_2") (pintype "unspecified"))
      (node (ref "USB1") (pin "3") (pinfunction "SHELL_3") (pintype "unspecified"))
      (node (ref "USB1") (pin "4") (pinfunction "SHELL_4") (pintype "unspecified"))
      (node (ref "USB1") (pin "A1B12") (pinfunction "GND_A1B12") (pintype "unspecified"))
      (node (ref "USB1") (pin "B1A12") (pinfunction "GND_B1A12") (pintype "unspecified"))
    )
    (net (code "55") (name "Net-(LED1-K)") (class "Default")
      (node (ref "LED1") (pin "1") (pinfunction "K_1") (pintype "unspecified"))
      (node (ref "R6") (pin "2") (pinfunction "2_2") (pintype "input"))
    )
    (net (code "56") (name "Net-(LED2-K)") (class "Default")
      (node (ref "LED2") (pin "1") (pinfunction "K_1") (pintype "unspecified"))
      (node (ref "R7") (pin "2") (pinfunction "2_2") (pintype "input"))
    )
    (net (code "57") (name "Net-(LED3-K)") (class "Default")
      (node (ref "LED3") (pin "1") (pinfunction "K_1") (pintype "unspecified"))
      (node (ref "R8") (pin "2") (pinfunction "2_2") (pintype "input"))
    )
    (net (code "58") (name "Net-(LED4-K)") (class "Default")
      (node (ref "LED4") (pin "1") (pinfunction "K_1") (pintype "unspecified"))
      (node (ref "R9") (pin "2") (pinfunction "2_2") (pintype "input"))
    )
    (net (code "59") (name "Net-(LED5-K)") (class "Default")
      (node (ref "LED5") (pin "1") (pinfunction "K_1") (pintype "unspecified"))
      (node (ref "R10") (pin "2") (pinfunction "2_2") (pintype "input"))
    )
    (net (code "60") (name "Net-(R11-Pad1)") (class "Default")
      (node (ref "R11") (pin "1") (pinfunction "1_1") (pintype "input"))
      (node (ref "SW1") (pin "2") (pinfunction "2_2") (pintype "unspecified"))
    )
    (net (code "61") (name "Net-(U1-USB_DM)") (class "Default")
      (node (ref "R5") (pin "1") (pinfunction "1_1") (pintype "unspecified"))
      (node (ref "U1") (pin "51") (pinfunction "USB_DM_51") (pintype "unspecified"))
    )
    (net (code "62") (name "Net-(U1-USB_DP)") (class "Default")
      (node (ref "R4") (pin "1") (pinfunction "1_1") (pintype "unspecified"))
      (node (ref "U1") (pin "52") (pinfunction "USB_DP_52") (pintype "unspecified"))
    )
    (net (code "63") (name "Net-(U4-REGOUT)") (class "Default")
      (node (ref "C19") (pin "1") (pinfunction "1_1") (pintype "unspecified"))
      (node (ref "U4") (pin "10") (pinfunction "REGOUT_10") (pintype "unspecified"))
    )
    (net (code "64") (name "Net-(USB1-CC1)") (class "Default")
      (node (ref "R2") (pin "1") (pinfunction "1_1") (pintype "input"))
      (node (ref "USB1") (pin "A5") (pinfunction "CC1_A5") (pintype "unspecified"))
    )
    (net (code "65") (name "Net-(USB1-CC2)") (class "Default")
      (node (ref "R3") (pin "1") (pinfunction "1_1") (pintype "input"))
      (node (ref "USB1") (pin "B5") (pinfunction "CC2_B5") (pintype "unspecified"))
    )
    (net (code "66") (name "VBUS") (class "Default")
      (node (ref "C20") (pin "2") (pinfunction "2_2") (pintype "input"))
      (node (ref "C22") (pin "2") (pinfunction "2_2") (pintype "input"))
      (node (ref "LED1") (pin "2") (pinfunction "A_2") (pintype "unspecified"))
      (node (ref "U5") (pin "3") (pinfunction "VIN_3") (pintype "unspecified"))
      (node (ref "U6") (pin "3") (pinfunction "VIN_3") (pintype "unspecified"))
      (node (ref "USB1") (pin "A4B9") (pinfunction "VBUS_A4B9") (pintype "unspecified"))
      (node (ref "USB1") (pin "B4A9") (pinfunction "VBUS_B4A9") (pintype "unspecified"))
    )
    (net (code "67") (name "unconnected-(U4-AUX_CL-Pad7)") (class "Default")
      (node (ref "U4") (pin "7") (pinfunction "AUX_CL_7") (pintype "unspecified+no_connect"))
    )
    (net (code "68") (name "unconnected-(U4-AUX_DA-Pad21)") (class "Default")
      (node (ref "U4") (pin "21") (pinfunction "AUX_DA_21") (pintype "unspecified+no_connect"))
    )
    (net (code "69") (name "unconnected-(U4-EP-Pad25)") (class "Default")
      (node (ref "U4") (pin "25") (pinfunction "EP_25") (pintype "unspecified+no_connect"))
    )
    (net (code "70") (name "unconnected-(U4-FSYNC-Pad11)") (class "Default")
      (node (ref "U4") (pin "11") (pinfunction "FSYNC_11") (pintype "unspecified"))
    )
    (net (code "71") (name "unconnected-(U4-INT1-Pad12)") (class "Default")
      (node (ref "U4") (pin "12") (pinfunction "INT1_12") (pintype "unspecified+no_connect"))
    )
    (net (code "72") (name "unconnected-(U4-NC-Pad1)") (class "Default")
      (node (ref "U4") (pin "1") (pinfunction "NC_1") (pintype "unspecified+no_connect"))
    )
    (net (code "73") (name "unconnected-(U4-NC-Pad2)") (class "Default")
      (node (ref "U4") (pin "2") (pinfunction "NC_2") (pintype "unspecified+no_connect"))
    )
    (net (code "74") (name "unconnected-(U4-NC-Pad3)") (class "Default")
      (node (ref "U4") (pin "3") (pinfunction "NC_3") (pintype "unspecified+no_connect"))
    )
    (net (code "75") (name "unconnected-(U4-NC-Pad4)") (class "Default")
      (node (ref "U4") (pin "4") (pinfunction "NC_4") (pintype "unspecified+no_connect"))
    )
    (net (code "76") (name "unconnected-(U4-NC-Pad5)") (class "Default")
      (node (ref "U4") (pin "5") (pinfunction "NC_5") (pintype "unspecified+no_connect"))
    )
    (net (code "77") (name "unconnected-(U4-NC-Pad6)") (class "Default")
      (node (ref "U4") (pin "6") (pinfunction "NC_6") (pintype "unspecified+no_connect"))
    )
    (net (code "78") (name "unconnected-(U4-NC-Pad14)") (class "Default")
      (node (ref "U4") (pin "14") (pinfunction "NC_14") (pintype "unspecified+no_connect"))
    )
    (net (code "79") (name "unconnected-(U4-NC-Pad15)") (class "Default")
      (node (ref "U4") (pin "15") (pinfunction "NC_15") (pintype "unspecified+no_connect"))
    )
    (net (code "80") (name "unconnected-(U4-NC-Pad16)") (class "Default")
      (node (ref "U4") (pin "16") (pinfunction "NC_16") (pintype "unspecified+no_connect"))
    )
    (net (code "81") (name "unconnected-(U4-NC-Pad17)") (class "Default")
      (node (ref "U4") (pin "17") (pinfunction "NC_17") (pintype "unspecified+no_connect"))
    )
    (net (code "82") (name "unconnected-(U4-RESV-Pad19)") (class "Default")
      (node (ref "U4") (pin "19") (pinfunction "RESV_19") (pintype "unspecified+no_connect"))
    )
    (net (code "83") (name "unconnected-(USB1-SBU1-PadA8)") (class "Default")
      (node (ref "USB1") (pin "A8") (pinfunction "SBU1_A8") (pintype "unspecified+no_connect"))
    )
    (net (code "84") (name "unconnected-(USB1-SBU2-PadB8)") (class "Default")
      (node (ref "USB1") (pin "B8") (pinfunction "SBU2_B8") (pintype "unspecified+no_connect"))
    )
  )
)
